# Sheet_1_2025-10-18_1.net
KiCad netlist of a schematic drawn in Altium Designer
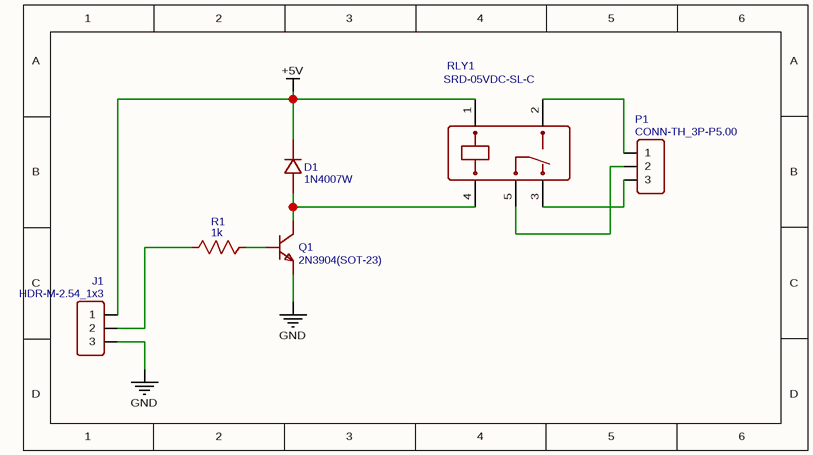
[diagram p0: Sheet_1_2025-10-18 (1).schdoc]

(export (version "E")
  (design (tool "Eeschema 10.0.6"))
  (components
    (comp (ref "D1")
      (value "1N4007W")
      (fields (field (name "MANUFACTURER") "BLUE ROCKET") (field (name "CONTRIBUTOR") "LCEDA_Lib"))
      (libsource (lib "altium-import") (part "root_1_1N4007W_"))
    )
    (comp (ref "J1")
      (value "HDR-M-2.54_1x3")
      (fields (field (name "CONTRIBUTOR") "LCEDA_Lib"))
      (libsource (lib "altium-import") (part "root_0_HDR-M-2.54_1x3_"))
    )
    (comp (ref "P1")
      (value "CONN-TH_3P-P5.00")
      (fields (field (name "CONTRIBUTOR") "LCEDA_Lib"))
      (libsource (lib "altium-import") (part "root_0_CONN-TH_3P-P5.00_"))
    )
    (comp (ref "Q1")
      (value "2N3904(SOT-23)")
      (fields
        (field (name "MANUFACTURER") "KEC")
        (field (name "MANUFACTURER PART") "2n3904S-RTK/PS")
        (field (name "CONTRIBUTOR") "LCEDA_Lib")
      )
      (libsource (lib "altium-import") (part "root_0_2N3904(SOT-23)_"))
    )
    (comp (ref "R1")
      (value "1k")
      (fields (field (name "CONTRIBUTOR") "LCEDA_Lib"))
      (libsource (lib "altium-import") (part "root_0_1k_"))
    )
    (comp (ref "RLY1")
      (value "SRD-05VDC-SL-C")
      (fields (field (name "MANUFACTURER") "松乐"))
      (libsource (lib "altium-import") (part "root_3_SRD-05VDC-SL-C_"))
    )
  )
  (nets
    (net (code "1") (name "+5V") (class "Default")
      (node (ref "D1") (pin "1") (pinfunction "1_1") (pintype "passive"))
      (node (ref "J1") (pin "1") (pinfunction "1_1") (pintype "passive"))
      (node (ref "RLY1") (pin "1") (pinfunction "1_1") (pintype "passive"))
    )
    (net (code "2") (name "GND") (class "Default")
      (node (ref "J1") (pin "3") (pinfunction "3_3") (pintype "passive"))
      (node (ref "Q1") (pin "1") (pinfunction "E_1") (pintype "passive"))
    )
    (net (code "3") (name "Net-(J1-Pad2)") (class "Default")
      (node (ref "J1") (pin "2") (pinfunction "2_2") (pintype "passive"))
      (node (ref "R1") (pin "1") (pinfunction "1_1") (pintype "passive"))
    )
    (net (code "4") (name "Net-(P1-Pad1)") (class "Default")
      (node (ref "P1") (pin "1") (pinfunction "1_1") (pintype "passive"))
      (node (ref "RLY1") (pin "2") (pinfunction "2_2") (pintype "passive"))
    )
    (net (code "5") (name "Net-(P1-Pad2)") (class "Default")
      (node (ref "P1") (pin "2") (pinfunction "2_2") (pintype "passive"))
      (node (ref "RLY1") (pin "5") (pinfunction "5_5") (pintype "passive"))
    )
    (net (code "6") (name "Net-(P1-Pad3)") (class "Default")
      (node (ref "P1") (pin "3") (pinfunction "3_3") (pintype "passive"))
      (node (ref "RLY1") (pin "3") (pinfunction "3_3") (pintype "passive"))
    )
    (net (code "7") (name "Net-(Q1-B)") (class "Default")
      (node (ref "Q1") (pin "2") (pinfunction "B_2") (pintype "passive"))
      (node (ref "R1") (pin "2") (pinfunction "2_2") (pintype "passive"))
    )
    (net (code "8") (name "Net-(Q1-C)") (class "Default")
      (node (ref "D1") (pin "2") (pinfunction "2_2") (pintype "passive"))
      (node (ref "Q1") (pin "3") (pinfunction "C_3") (pintype "passive"))
      (node (ref "RLY1") (pin "4") (pinfunction "4_4") (pintype "passive"))
    )
  )
)
